# M205A.net
KiCad netlist of a schematic drawn in EAGLE
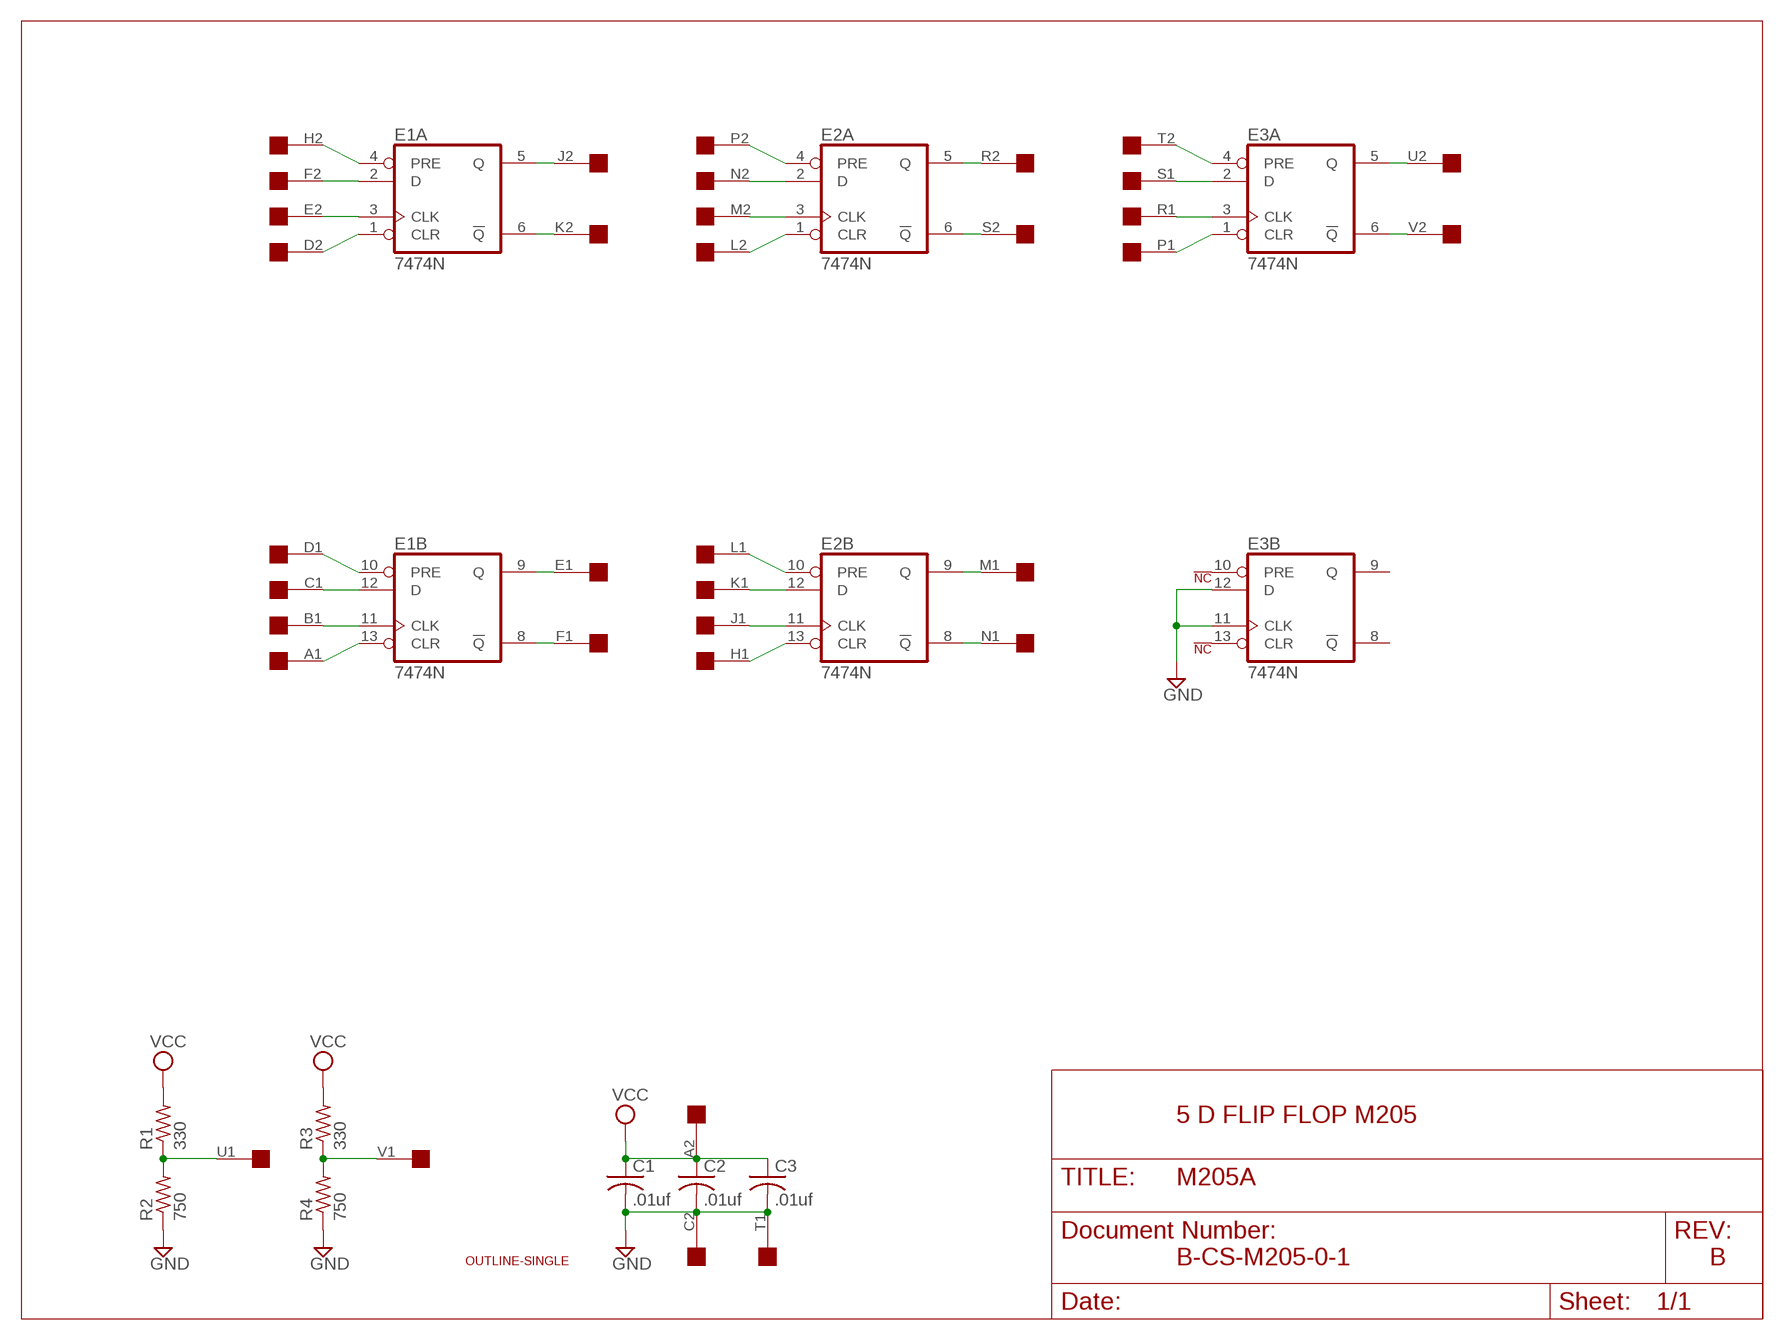
[diagram p0: schematic, sheet 1]

(export (version "E")
  (design (tool "Eeschema 10.0.6"))
  (components
    (comp (ref "C1")
      (value ".01uf")
      (footprint "eagle-import:C050-025X075")
      (libsource (lib "eagle-import") (part "C-US050-025X075"))
    )
    (comp (ref "C2")
      (value ".01uf")
      (footprint "eagle-import:C050-025X075")
      (libsource (lib "eagle-import") (part "C-US050-025X075"))
    )
    (comp (ref "C3")
      (value ".01uf")
      (footprint "eagle-import:C050-025X075")
      (libsource (lib "eagle-import") (part "C-US050-025X075"))
    )
    (comp (ref "E1")
      (value "7474N")
      (footprint "eagle-import:DIL14")
      (libsource (lib "eagle-import") (part "7474NS"))
    )
    (comp (ref "E2")
      (value "7474N")
      (footprint "eagle-import:DIL14")
      (libsource (lib "eagle-import") (part "7474NS"))
    )
    (comp (ref "E3")
      (value "7474N")
      (footprint "eagle-import:DIL14")
      (libsource (lib "eagle-import") (part "7474NS"))
    )
    (comp (ref "R1")
      (value "330")
      (footprint "eagle-import:0207_10")
      (libsource (lib "eagle-import") (part "R-US_0207/10"))
    )
    (comp (ref "R2")
      (value "750")
      (footprint "eagle-import:0207_10")
      (libsource (lib "eagle-import") (part "R-US_0207/10"))
    )
    (comp (ref "R3")
      (value "330")
      (footprint "eagle-import:0207_10")
      (libsource (lib "eagle-import") (part "R-US_0207/10"))
    )
    (comp (ref "R4")
      (value "750")
      (footprint "eagle-import:0207_10")
      (libsource (lib "eagle-import") (part "R-US_0207/10"))
    )
    (comp (ref "U$1")
      (value "OUTLINE-SINGLE")
      (footprint "eagle-import:SINGLE")
      (libsource (lib "eagle-import") (part "OUTLINE-SINGLE"))
    )
    (comp (ref "U$2")
      (value "EDGE-2CONNECTOR")
      (footprint "eagle-import:EDGE-CON2")
      (libsource (lib "eagle-import") (part "EDGE-2CONNECTOR"))
    )
  )
  (nets
    (net (code "1") (name "GND") (class "Default")
      (node (ref "C1") (pin "2") (pinfunction "2_2") (pintype "passive"))
      (node (ref "C2") (pin "2") (pinfunction "2_2") (pintype "passive"))
      (node (ref "C3") (pin "2") (pinfunction "2_2") (pintype "passive"))
      (node (ref "E3") (pin "11") (pinfunction "CLK_11") (pintype "input"))
      (node (ref "E3") (pin "12") (pinfunction "D_12") (pintype "input"))
      (node (ref "R2") (pin "1") (pinfunction "1_1") (pintype "passive"))
      (node (ref "R4") (pin "1") (pinfunction "1_1") (pintype "passive"))
      (node (ref "U$2") (pin "C2") (pinfunction "1_C2") (pintype "bidirectional"))
      (node (ref "U$2") (pin "T1") (pinfunction "1_T1") (pintype "bidirectional"))
    )
    (net (code "2") (name "NC") (class "Default")
      (node (ref "E3") (pin "10") (pinfunction "PRE_10") (pintype "input"))
      (node (ref "E3") (pin "13") (pinfunction "CLR_13") (pintype "input"))
    )
    (net (code "3") (name "Net-(E1A-CLK)") (class "Default")
      (node (ref "E1") (pin "3") (pinfunction "CLK_3") (pintype "input"))
      (node (ref "U$2") (pin "E2") (pinfunction "1_E2") (pintype "bidirectional"))
    )
    (net (code "4") (name "Net-(E1A-CLR)") (class "Default")
      (node (ref "E1") (pin "1") (pinfunction "CLR_1") (pintype "input"))
      (node (ref "U$2") (pin "D2") (pinfunction "1_D2") (pintype "bidirectional"))
    )
    (net (code "5") (name "Net-(E1A-D)") (class "Default")
      (node (ref "E1") (pin "2") (pinfunction "D_2") (pintype "input"))
      (node (ref "U$2") (pin "F2") (pinfunction "1_F2") (pintype "bidirectional"))
    )
    (net (code "6") (name "Net-(E1A-PRE)") (class "Default")
      (node (ref "E1") (pin "4") (pinfunction "PRE_4") (pintype "input"))
      (node (ref "U$2") (pin "H2") (pinfunction "1_H2") (pintype "bidirectional"))
    )
    (net (code "7") (name "Net-(E1A-Q)") (class "Default")
      (node (ref "E1") (pin "5") (pinfunction "Q_5") (pintype "output"))
      (node (ref "U$2") (pin "J2") (pinfunction "1_J2") (pintype "bidirectional"))
    )
    (net (code "8") (name "Net-(E1A-~{Q})") (class "Default")
      (node (ref "E1") (pin "6") (pinfunction "~{Q}_6") (pintype "output"))
      (node (ref "U$2") (pin "K2") (pinfunction "1_K2") (pintype "bidirectional"))
    )
    (net (code "9") (name "Net-(E1B-CLK)") (class "Default")
      (node (ref "E1") (pin "11") (pinfunction "CLK_11") (pintype "input"))
      (node (ref "U$2") (pin "B1") (pinfunction "1_B1") (pintype "bidirectional"))
    )
    (net (code "10") (name "Net-(E1B-CLR)") (class "Default")
      (node (ref "E1") (pin "13") (pinfunction "CLR_13") (pintype "input"))
      (node (ref "U$2") (pin "A1") (pinfunction "1_A1") (pintype "bidirectional"))
    )
    (net (code "11") (name "Net-(E1B-D)") (class "Default")
      (node (ref "E1") (pin "12") (pinfunction "D_12") (pintype "input"))
      (node (ref "U$2") (pin "C1") (pinfunction "1_C1") (pintype "bidirectional"))
    )
    (net (code "12") (name "Net-(E1B-PRE)") (class "Default")
      (node (ref "E1") (pin "10") (pinfunction "PRE_10") (pintype "input"))
      (node (ref "U$2") (pin "D1") (pinfunction "1_D1") (pintype "bidirectional"))
    )
    (net (code "13") (name "Net-(E1B-Q)") (class "Default")
      (node (ref "E1") (pin "9") (pinfunction "Q_9") (pintype "output"))
      (node (ref "U$2") (pin "E1") (pinfunction "1_E1") (pintype "bidirectional"))
    )
    (net (code "14") (name "Net-(E1B-~{Q})") (class "Default")
      (node (ref "E1") (pin "8") (pinfunction "~{Q}_8") (pintype "output"))
      (node (ref "U$2") (pin "F1") (pinfunction "1_F1") (pintype "bidirectional"))
    )
    (net (code "15") (name "Net-(E2A-CLK)") (class "Default")
      (node (ref "E2") (pin "3") (pinfunction "CLK_3") (pintype "input"))
      (node (ref "U$2") (pin "M2") (pinfunction "1_M2") (pintype "bidirectional"))
    )
    (net (code "16") (name "Net-(E2A-CLR)") (class "Default")
      (node (ref "E2") (pin "1") (pinfunction "CLR_1") (pintype "input"))
      (node (ref "U$2") (pin "L2") (pinfunction "1_L2") (pintype "bidirectional"))
    )
    (net (code "17") (name "Net-(E2A-D)") (class "Default")
      (node (ref "E2") (pin "2") (pinfunction "D_2") (pintype "input"))
      (node (ref "U$2") (pin "N2") (pinfunction "1_N2") (pintype "bidirectional"))
    )
    (net (code "18") (name "Net-(E2A-PRE)") (class "Default")
      (node (ref "E2") (pin "4") (pinfunction "PRE_4") (pintype "input"))
      (node (ref "U$2") (pin "P2") (pinfunction "1_P2") (pintype "bidirectional"))
    )
    (net (code "19") (name "Net-(E2A-Q)") (class "Default")
      (node (ref "E2") (pin "5") (pinfunction "Q_5") (pintype "output"))
      (node (ref "U$2") (pin "R2") (pinfunction "1_R2") (pintype "bidirectional"))
    )
    (net (code "20") (name "Net-(E2A-~{Q})") (class "Default")
      (node (ref "E2") (pin "6") (pinfunction "~{Q}_6") (pintype "output"))
      (node (ref "U$2") (pin "S2") (pinfunction "1_S2") (pintype "bidirectional"))
    )
    (net (code "21") (name "Net-(E2B-CLK)") (class "Default")
      (node (ref "E2") (pin "11") (pinfunction "CLK_11") (pintype "input"))
      (node (ref "U$2") (pin "J1") (pinfunction "1_J1") (pintype "bidirectional"))
    )
    (net (code "22") (name "Net-(E2B-CLR)") (class "Default")
      (node (ref "E2") (pin "13") (pinfunction "CLR_13") (pintype "input"))
      (node (ref "U$2") (pin "H1") (pinfunction "1_H1") (pintype "bidirectional"))
    )
    (net (code "23") (name "Net-(E2B-D)") (class "Default")
      (node (ref "E2") (pin "12") (pinfunction "D_12") (pintype "input"))
      (node (ref "U$2") (pin "K1") (pinfunction "1_K1") (pintype "bidirectional"))
    )
    (net (code "24") (name "Net-(E2B-PRE)") (class "Default")
      (node (ref "E2") (pin "10") (pinfunction "PRE_10") (pintype "input"))
      (node (ref "U$2") (pin "L1") (pinfunction "1_L1") (pintype "bidirectional"))
    )
    (net (code "25") (name "Net-(E2B-Q)") (class "Default")
      (node (ref "E2") (pin "9") (pinfunction "Q_9") (pintype "output"))
      (node (ref "U$2") (pin "M1") (pinfunction "1_M1") (pintype "bidirectional"))
    )
    (net (code "26") (name "Net-(E2B-~{Q})") (class "Default")
      (node (ref "E2") (pin "8") (pinfunction "~{Q}_8") (pintype "output"))
      (node (ref "U$2") (pin "N1") (pinfunction "1_N1") (pintype "bidirectional"))
    )
    (net (code "27") (name "Net-(E3A-CLK)") (class "Default")
      (node (ref "E3") (pin "3") (pinfunction "CLK_3") (pintype "input"))
      (node (ref "U$2") (pin "R1") (pinfunction "1_R1") (pintype "bidirectional"))
    )
    (net (code "28") (name "Net-(E3A-CLR)") (class "Default")
      (node (ref "E3") (pin "1") (pinfunction "CLR_1") (pintype "input"))
      (node (ref "U$2") (pin "P1") (pinfunction "1_P1") (pintype "bidirectional"))
    )
    (net (code "29") (name "Net-(E3A-D)") (class "Default")
      (node (ref "E3") (pin "2") (pinfunction "D_2") (pintype "input"))
      (node (ref "U$2") (pin "S1") (pinfunction "1_S1") (pintype "bidirectional"))
    )
    (net (code "30") (name "Net-(E3A-PRE)") (class "Default")
      (node (ref "E3") (pin "4") (pinfunction "PRE_4") (pintype "input"))
      (node (ref "U$2") (pin "T2") (pinfunction "1_T2") (pintype "bidirectional"))
    )
    (net (code "31") (name "Net-(E3A-Q)") (class "Default")
      (node (ref "E3") (pin "5") (pinfunction "Q_5") (pintype "output"))
      (node (ref "U$2") (pin "U2") (pinfunction "1_U2") (pintype "bidirectional"))
    )
    (net (code "32") (name "Net-(E3A-~{Q})") (class "Default")
      (node (ref "E3") (pin "6") (pinfunction "~{Q}_6") (pintype "output"))
      (node (ref "U$2") (pin "V2") (pinfunction "1_V2") (pintype "bidirectional"))
    )
    (net (code "33") (name "Net-(U$2AG-1)") (class "Default")
      (node (ref "R1") (pin "1") (pinfunction "1_1") (pintype "passive"))
      (node (ref "R2") (pin "2") (pinfunction "2_2") (pintype "passive"))
      (node (ref "U$2") (pin "U1") (pinfunction "1_U1") (pintype "bidirectional"))
    )
    (net (code "34") (name "Net-(U$2AI-1)") (class "Default")
      (node (ref "R3") (pin "1") (pinfunction "1_1") (pintype "passive"))
      (node (ref "R4") (pin "2") (pinfunction "2_2") (pintype "passive"))
      (node (ref "U$2") (pin "V1") (pinfunction "1_V1") (pintype "bidirectional"))
    )
    (net (code "35") (name "VCC") (class "Default")
      (node (ref "C1") (pin "1") (pinfunction "1_1") (pintype "passive"))
      (node (ref "C2") (pin "1") (pinfunction "1_1") (pintype "passive"))
      (node (ref "C3") (pin "1") (pinfunction "1_1") (pintype "passive"))
      (node (ref "R1") (pin "2") (pinfunction "2_2") (pintype "passive"))
      (node (ref "R3") (pin "2") (pinfunction "2_2") (pintype "passive"))
      (node (ref "U$2") (pin "A2") (pinfunction "1_A2") (pintype "bidirectional"))
    )
    (net (code "36") (name "unconnected-(E3B-Q-Pad9)") (class "Default")
      (node (ref "E3") (pin "9") (pinfunction "Q_9") (pintype "output"))
    )
    (net (code "37") (name "unconnected-(E3B-~{Q}-Pad8)") (class "Default")
      (node (ref "E3") (pin "8") (pinfunction "~{Q}_8") (pintype "output"))
    )
  )
)
